# GRLV_DoubleRail_Part2_V0_1.net
KiCad netlist of a schematic drawn in Altium Designer
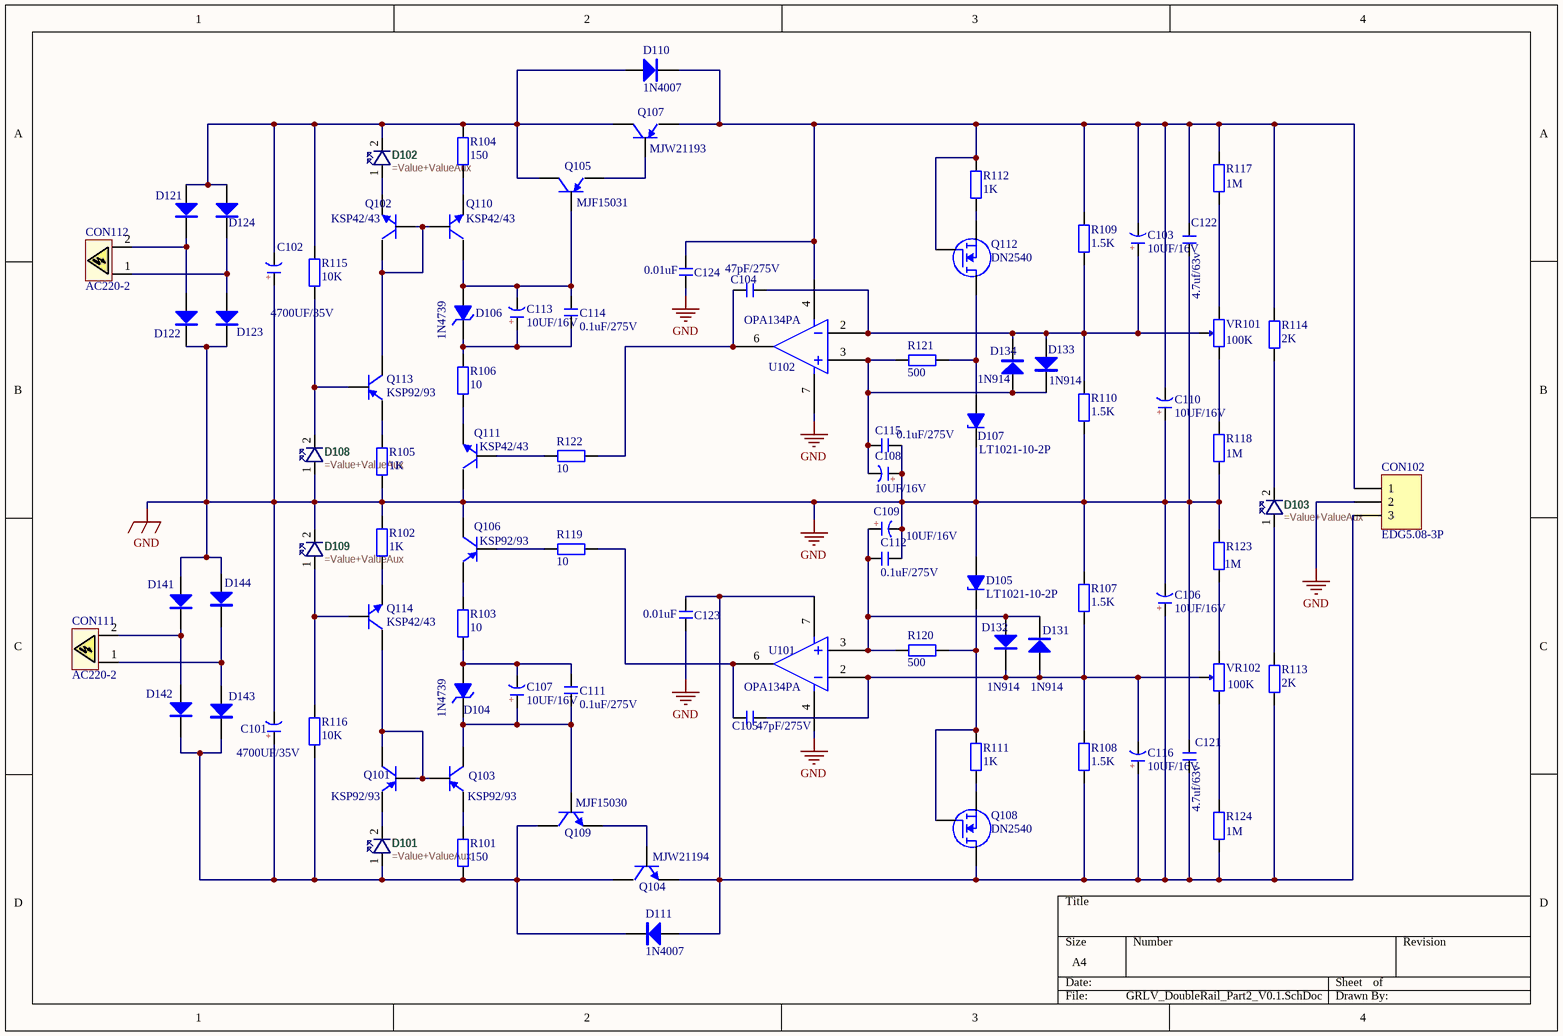
[diagram p0: GRLV_DoubleRail_Part2_V0.1.SchDoc]

(export (version "E")
  (design (tool "Eeschema 10.0.6"))
  (components
    (comp (ref "C101")
      (value "4700UF/35V")
      (footprint "CAP 11*35*60")
      (description "直插电解电容")
      (fields (field (name "版权归属") "源创客"))
      (libsource (lib "电阻-电容-电感") (part "C-CAP"))
    )
    (comp (ref "C102")
      (value "4700UF/35V")
      (footprint "CAP 11*35*60")
      (description "直插电解电容")
      (fields (field (name "版权归属") "源创客"))
      (libsource (lib "电阻-电容-电感") (part "C-CAP"))
    )
    (comp (ref "C103")
      (value "10UF/16V")
      (footprint "CAP 1.5*4*8")
      (description "直插电解电容")
      (fields (field (name "版权归属") "源创客"))
      (libsource (lib "电阻-电容-电感") (part "C-CAP"))
    )
    (comp (ref "C104")
      (value "47pF/275V")
      (footprint "CBB 6.3*6.3*5")
      (description "CBB电容")
      (fields (field (name "版权归属") "源创客"))
      (libsource (lib "电阻-电容-电感") (part "C-CBB"))
    )
    (comp (ref "C105")
      (value "47pF/275V")
      (footprint "CBB 6.3*6.3*5")
      (description "CBB电容")
      (fields (field (name "版权归属") "源创客"))
      (libsource (lib "电阻-电容-电感") (part "C-CBB"))
    )
    (comp (ref "C106")
      (value "10UF/16V")
      (footprint "CAP 3.5*8*11.5")
      (description "直插电解电容")
      (fields (field (name "版权归属") "源创客"))
      (libsource (lib "电阻-电容-电感") (part "C-CAP"))
    )
    (comp (ref "C107")
      (value "10UF/16V")
      (footprint "CAP 1.5*4*8")
      (description "直插电解电容")
      (fields (field (name "版权归属") "源创客"))
      (libsource (lib "电阻-电容-电感") (part "C-CAP"))
    )
    (comp (ref "C108")
      (value "10UF/16V")
      (footprint "CAP 1.5*4*8")
      (description "直插电解电容")
      (fields (field (name "版权归属") "源创客"))
      (libsource (lib "") (part "C-CAP_1"))
    )
    (comp (ref "C109")
      (value "10UF/16V")
      (footprint "CAP 1.5*4*8")
      (description "直插电解电容")
      (fields (field (name "版权归属") "源创客"))
      (libsource (lib "") (part "C-CAP_1"))
    )
    (comp (ref "C110")
      (value "10UF/16V")
      (footprint "CAP 3.5*8*11.5")
      (description "直插电解电容")
      (fields (field (name "版权归属") "源创客"))
      (libsource (lib "电阻-电容-电感") (part "C-CAP"))
    )
    (comp (ref "C111")
      (value "0.1uF/275V")
      (footprint "CBB 6.3*6.3*5")
      (description "CBB电容")
      (fields (field (name "版权归属") "源创客"))
      (libsource (lib "电阻-电容-电感") (part "C-CBB"))
    )
    (comp (ref "C112")
      (value "0.1uF/275V")
      (footprint "CBB 6.3*6.3*5")
      (description "CBB电容")
      (fields (field (name "版权归属") "源创客"))
      (libsource (lib "电阻-电容-电感") (part "C-CBB"))
    )
    (comp (ref "C113")
      (value "10UF/16V")
      (footprint "CAP 1.5*4*8")
      (description "直插电解电容")
      (fields (field (name "版权归属") "源创客"))
      (libsource (lib "电阻-电容-电感") (part "C-CAP"))
    )
    (comp (ref "C114")
      (value "0.1uF/275V")
      (footprint "CBB 6.3*6.3*5")
      (description "CBB电容")
      (fields (field (name "版权归属") "源创客"))
      (libsource (lib "电阻-电容-电感") (part "C-CBB"))
    )
    (comp (ref "C115")
      (value "0.1uF/275V")
      (footprint "CBB 6.3*6.3*5")
      (description "CBB电容")
      (fields (field (name "版权归属") "源创客"))
      (libsource (lib "电阻-电容-电感") (part "C-CBB"))
    )
    (comp (ref "C116")
      (value "10UF/16V")
      (footprint "CAP 1.5*4*8")
      (description "直插电解电容")
      (fields (field (name "版权归属") "源创客"))
      (libsource (lib "电阻-电容-电感") (part "C-CAP"))
    )
    (comp (ref "C121")
      (value "4.7uf/63v")
      (footprint "CBB 7.2*7.2*13")
      (description "MKS薄膜电容")
      (libsource (lib "电阻-电容-电感") (part "C-MKS"))
    )
    (comp (ref "C122")
      (value "4.7uf/63v")
      (footprint "CBB 7.2*7.2*13")
      (description "MKS薄膜电容")
      (libsource (lib "电阻-电容-电感") (part "C-MKS"))
    )
    (comp (ref "C123")
      (value "0.01uF")
      (footprint "CBB 6.3*6.3*5")
      (description "CBB电容")
      (fields (field (name "Comment") "0.01uF/275V") (field (name "版权归属") "源创客"))
      (libsource (lib "电阻-电容-电感") (part "C-CBB"))
    )
    (comp (ref "C124")
      (value "0.01uF")
      (footprint "CBB 6.3*6.3*5")
      (description "CBB电容")
      (fields (field (name "Comment") "0.01uF/275V") (field (name "版权归属") "源创客"))
      (libsource (lib "电阻-电容-电感") (part "C-CBB"))
    )
    (comp (ref "CON102")
      (value "EDG5.08-3P")
      (footprint "HX5.08-3S")
      (libsource (lib "Connectors") (part "EDG5.08-3P"))
    )
    (comp (ref "CON111")
      (value "AC220-2")
      (footprint "HX5.08-2S")
      (libsource (lib "Connectors") (part "AC220-2"))
    )
    (comp (ref "CON112")
      (value "AC220-2")
      (footprint "HX5.08-2S")
      (libsource (lib "Connectors") (part "AC220-2"))
    )
    (comp (ref "D101")
      (value "~")
      (footprint "LED 3MM-R")
      (description "直插式LED")
      (libsource (lib "LED") (part "LED"))
    )
    (comp (ref "D102")
      (value "~")
      (footprint "LED 3MM-R")
      (description "直插式LED")
      (libsource (lib "LED") (part "LED"))
    )
    (comp (ref "D103")
      (value "~")
      (footprint "LED 3MM-R")
      (description "直插式LED")
      (libsource (lib "LED") (part "LED"))
    )
    (comp (ref "D104")
      (value "1N4739")
      (footprint "DO-41")
      (description "9.1V/1W稳压管")
      (libsource (lib "二极管-整流桥") (part "1N4739"))
    )
    (comp (ref "D105")
      (value "LT1021-10-2P")
      (footprint "DIP8-300_MH")
      (description "10V Precision Reference 2 Pin Config")
      (libsource (lib "电压参考") (part "LT1021-10-2P"))
    )
    (comp (ref "D106")
      (value "1N4739")
      (footprint "DO-41")
      (description "9.1V/1W稳压管")
      (libsource (lib "二极管-整流桥") (part "1N4739"))
    )
    (comp (ref "D107")
      (value "LT1021-10-2P")
      (footprint "DIP8-300_MH")
      (description "10V Precision Reference 2 Pin Config")
      (libsource (lib "电压参考") (part "LT1021-10-2P"))
    )
    (comp (ref "D108")
      (value "~")
      (footprint "LED 3MM-R")
      (description "直插式LED")
      (libsource (lib "LED") (part "LED"))
    )
    (comp (ref "D109")
      (value "~")
      (footprint "LED 3MM-R")
      (description "直插式LED")
      (libsource (lib "LED") (part "LED"))
    )
    (comp (ref "D110")
      (value "1N4007")
      (footprint "DO-41")
      (description "整流二极管")
      (fields (field (name "版权归属") "源创客"))
      (libsource (lib "二极管-整流桥") (part "1N4007"))
    )
    (comp (ref "D111")
      (value "1N4007")
      (footprint "DO-41")
      (description "整流二极管")
      (fields (field (name "版权归属") "源创客"))
      (libsource (lib "二极管-整流桥") (part "1N4007"))
    )
    (comp (ref "D121")
      (value "VS-HFA08TB60-M3")
      (footprint "TO220AC")
      (description "Ultrafast Soft Recovery Diado 8A 600V")
      (libsource (lib "二极管-整流桥") (part "VS-HFA08TB60-M3"))
    )
    (comp (ref "D122")
      (value "VS-HFA08TB60-M3")
      (footprint "TO220AC")
      (description "Ultrafast Soft Recovery Diado 8A 600V")
      (libsource (lib "二极管-整流桥") (part "VS-HFA08TB60-M3"))
    )
    (comp (ref "D123")
      (value "VS-HFA08TB60-M3")
      (footprint "TO220AC")
      (description "Ultrafast Soft Recovery Diado 8A 600V")
      (libsource (lib "二极管-整流桥") (part "VS-HFA08TB60-M3"))
    )
    (comp (ref "D124")
      (value "VS-HFA08TB60-M3")
      (footprint "TO220AC")
      (description "Ultrafast Soft Recovery Diado 8A 600V")
      (libsource (lib "二极管-整流桥") (part "VS-HFA08TB60-M3"))
    )
    (comp (ref "D131")
      (value "1N914")
      (footprint "DO-35")
      (description "高速开关管 1V/0.25W")
      (libsource (lib "二极管-整流桥") (part "1N914"))
    )
    (comp (ref "D132")
      (value "1N914")
      (footprint "DO-35")
      (description "高速开关管 1V/0.25W")
      (libsource (lib "二极管-整流桥") (part "1N914"))
    )
    (comp (ref "D133")
      (value "1N914")
      (footprint "DO-35")
      (description "高速开关管 1V/0.25W")
      (libsource (lib "二极管-整流桥") (part "1N914"))
    )
    (comp (ref "D134")
      (value "1N914")
      (footprint "DO-35")
      (description "高速开关管 1V/0.25W")
      (libsource (lib "二极管-整流桥") (part "1N914"))
    )
    (comp (ref "D141")
      (value "VS-HFA08TB60-M3")
      (footprint "TO220AC")
      (description "Ultrafast Soft Recovery Diado 8A 600V")
      (libsource (lib "二极管-整流桥") (part "VS-HFA08TB60-M3"))
    )
    (comp (ref "D142")
      (value "VS-HFA08TB60-M3")
      (footprint "TO220AC")
      (description "Ultrafast Soft Recovery Diado 8A 600V")
      (libsource (lib "二极管-整流桥") (part "VS-HFA08TB60-M3"))
    )
    (comp (ref "D143")
      (value "VS-HFA08TB60-M3")
      (footprint "TO220AC")
      (description "Ultrafast Soft Recovery Diado 8A 600V")
      (libsource (lib "二极管-整流桥") (part "VS-HFA08TB60-M3"))
    )
    (comp (ref "D144")
      (value "VS-HFA08TB60-M3")
      (footprint "TO220AC")
      (description "Ultrafast Soft Recovery Diado 8A 600V")
      (libsource (lib "二极管-整流桥") (part "VS-HFA08TB60-M3"))
    )
    (comp (ref "Q101")
      (value "KSP92/93")
      (footprint "TO92A")
      (description "High Voltage PNP Transistor")
      (libsource (lib "三极管") (part "KSP92/93"))
    )
    (comp (ref "Q102")
      (value "KSP42/43")
      (footprint "TO92A")
      (description "High Voltage NPN Transistor")
      (libsource (lib "三极管") (part "KSP42/43"))
    )
    (comp (ref "Q103")
      (value "KSP92/93")
      (footprint "TO92A")
      (description "High Voltage PNP Transistor")
      (libsource (lib "三极管") (part "KSP92/93"))
    )
    (comp (ref "Q104")
      (value "MJW21194")
      (footprint "TO247V")
      (description "Power NPN Transistor")
      (libsource (lib "三极管") (part "MJW21194"))
    )
    (comp (ref "Q105")
      (value "MJF15031")
      (footprint "TO220V")
      (description "Power PNP Transistor")
      (libsource (lib "三极管") (part "MJF15031"))
    )
    (comp (ref "Q106")
      (value "KSP92/93")
      (footprint "TO92A")
      (description "High Voltage PNP Transistor")
      (libsource (lib "三极管") (part "KSP92/93"))
    )
    (comp (ref "Q107")
      (value "MJW21193")
      (footprint "TO247V")
      (description "Power PNP Transistor")
      (libsource (lib "三极管") (part "MJW21193"))
    )
    (comp (ref "Q108")
      (value "DN2540")
      (footprint "TO92A")
      (description "N沟道耗尽型DMOS场效应管 400V/150ma")
      (libsource (lib "场效应管") (part "DN2540"))
    )
    (comp (ref "Q109")
      (value "MJF15030")
      (footprint "TO220V")
      (description "Power NPN Transistor")
      (libsource (lib "三极管") (part "MJF15030"))
    )
    (comp (ref "Q110")
      (value "KSP42/43")
      (footprint "TO92A")
      (description "High Voltage NPN Transistor")
      (libsource (lib "三极管") (part "KSP42/43"))
    )
    (comp (ref "Q111")
      (value "KSP42/43")
      (footprint "TO92A")
      (description "High Voltage NPN Transistor")
      (libsource (lib "三极管") (part "KSP42/43"))
    )
    (comp (ref "Q112")
      (value "DN2540")
      (footprint "TO92A")
      (description "N沟道耗尽型DMOS场效应管 400V/150ma")
      (libsource (lib "场效应管") (part "DN2540"))
    )
    (comp (ref "Q113")
      (value "KSP92/93")
      (footprint "TO92A")
      (description "High Voltage PNP Transistor")
      (libsource (lib "三极管") (part "KSP92/93"))
    )
    (comp (ref "Q114")
      (value "KSP42/43")
      (footprint "TO92A")
      (description "High Voltage NPN Transistor")
      (libsource (lib "三极管") (part "KSP42/43"))
    )
    (comp (ref "R101")
      (value "150")
      (footprint "RS 1/4W")
      (description "直插色环电阻")
      (fields (field (name "版权归属") "源创客"))
      (libsource (lib "电阻-电容-电感") (part "R-CRR"))
    )
    (comp (ref "R102")
      (value "1K")
      (footprint "RS 1/4W")
      (description "直插色环电阻")
      (fields (field (name "版权归属") "源创客"))
      (libsource (lib "电阻-电容-电感") (part "R-CRR"))
    )
    (comp (ref "R103")
      (value "10")
      (footprint "RS 1/4W")
      (description "直插色环电阻")
      (fields (field (name "版权归属") "源创客"))
      (libsource (lib "电阻-电容-电感") (part "R-CRR"))
    )
    (comp (ref "R104")
      (value "150")
      (footprint "RS 1/4W")
      (description "直插色环电阻")
      (fields (field (name "版权归属") "源创客"))
      (libsource (lib "电阻-电容-电感") (part "R-CRR"))
    )
    (comp (ref "R105")
      (value "1K")
      (footprint "RS 1/4W")
      (description "直插色环电阻")
      (fields (field (name "版权归属") "源创客"))
      (libsource (lib "电阻-电容-电感") (part "R-CRR"))
    )
    (comp (ref "R106")
      (value "10")
      (footprint "RS 1/4W")
      (description "直插色环电阻")
      (fields (field (name "版权归属") "源创客"))
      (libsource (lib "电阻-电容-电感") (part "R-CRR"))
    )
    (comp (ref "R107")
      (value "1.5K")
      (footprint "RS 1/4W")
      (description "直插色环电阻")
      (fields (field (name "版权归属") "源创客"))
      (libsource (lib "电阻-电容-电感") (part "R-CRR"))
    )
    (comp (ref "R108")
      (value "1.5K")
      (footprint "RS 1/4W")
      (description "直插色环电阻")
      (fields (field (name "版权归属") "源创客"))
      (libsource (lib "电阻-电容-电感") (part "R-CRR"))
    )
    (comp (ref "R109")
      (value "1.5K")
      (footprint "RS 1/4W")
      (description "直插色环电阻")
      (fields (field (name "版权归属") "源创客"))
      (libsource (lib "电阻-电容-电感") (part "R-CRR"))
    )
    (comp (ref "R110")
      (value "1.5K")
      (footprint "RS 1/4W")
      (description "直插色环电阻")
      (fields (field (name "版权归属") "源创客"))
      (libsource (lib "电阻-电容-电感") (part "R-CRR"))
    )
    (comp (ref "R111")
      (value "1K")
      (footprint "RS 1/4W")
      (description "直插色环电阻")
      (fields (field (name "版权归属") "源创客"))
      (libsource (lib "电阻-电容-电感") (part "R-CRR"))
    )
    (comp (ref "R112")
      (value "1K")
      (footprint "RS 1/4W")
      (description "直插色环电阻")
      (fields (field (name "版权归属") "源创客"))
      (libsource (lib "电阻-电容-电感") (part "R-CRR"))
    )
    (comp (ref "R113")
      (value "2K")
      (footprint "RS 1/4W")
      (description "直插色环电阻")
      (fields (field (name "版权归属") "源创客"))
      (libsource (lib "电阻-电容-电感") (part "R-CRR"))
    )
    (comp (ref "R114")
      (value "2K")
      (footprint "RS 1/4W")
      (description "直插色环电阻")
      (fields (field (name "版权归属") "源创客"))
      (libsource (lib "电阻-电容-电感") (part "R-CRR"))
    )
    (comp (ref "R115")
      (value "10K")
      (footprint "RS 1/4W")
      (description "直插色环电阻")
      (fields (field (name "版权归属") "源创客"))
      (libsource (lib "电阻-电容-电感") (part "R-CRR"))
    )
    (comp (ref "R116")
      (value "10K")
      (footprint "RS 1/4W")
      (description "直插色环电阻")
      (fields (field (name "版权归属") "源创客"))
      (libsource (lib "电阻-电容-电感") (part "R-CRR"))
    )
    (comp (ref "R117")
      (value "1M")
      (footprint "RS 1/4W")
      (description "直插色环电阻")
      (fields (field (name "版权归属") "源创客"))
      (libsource (lib "电阻-电容-电感") (part "R-CRR"))
    )
    (comp (ref "R118")
      (value "1M")
      (footprint "RS 1/4W")
      (description "直插色环电阻")
      (fields (field (name "版权归属") "源创客"))
      (libsource (lib "电阻-电容-电感") (part "R-CRR"))
    )
    (comp (ref "R119")
      (value "10")
      (footprint "RS 1/4W")
      (description "直插色环电阻")
      (fields (field (name "版权归属") "源创客"))
      (libsource (lib "电阻-电容-电感") (part "R-CRR"))
    )
    (comp (ref "R120")
      (value "500")
      (footprint "RS 1/4W")
      (description "直插色环电阻")
      (fields (field (name "版权归属") "源创客"))
      (libsource (lib "电阻-电容-电感") (part "R-CRR"))
    )
    (comp (ref "R121")
      (value "500")
      (footprint "RS 1/4W")
      (description "直插色环电阻")
      (fields (field (name "版权归属") "源创客"))
      (libsource (lib "电阻-电容-电感") (part "R-CRR"))
    )
    (comp (ref "R122")
      (value "10")
      (footprint "RS 1/4W")
      (description "直插色环电阻")
      (fields (field (name "版权归属") "源创客"))
      (libsource (lib "电阻-电容-电感") (part "R-CRR"))
    )
    (comp (ref "R123")
      (value "1M")
      (footprint "RS 1/4W")
      (description "直插色环电阻")
      (fields (field (name "版权归属") "源创客"))
      (libsource (lib "电阻-电容-电感") (part "R-CRR"))
    )
    (comp (ref "R124")
      (value "1M")
      (footprint "RS 1/4W")
      (description "直插色环电阻")
      (fields (field (name "版权归属") "源创客"))
      (libsource (lib "电阻-电容-电感") (part "R-CRR"))
    )
    (comp (ref "U101") (value "OPA134PA") (footprint "DIP8-300_MH") (libsource (lib "运放") (part "OPA134PA")))
    (comp (ref "U102") (value "OPA134PA") (footprint "DIP8-300_MH") (libsource (lib "运放") (part "OPA134PA")))
    (comp (ref "VR101")
      (value "100K")
      (footprint "RS 1/2W-VR")
      (description "直插可调电阻-顶调")
      (fields (field (name "Comment") "VR-W"))
      (libsource (lib "电阻-电容-电感") (part "VR-W"))
    )
    (comp (ref "VR102")
      (value "100K")
      (footprint "RS 1/2W-VR")
      (description "直插可调电阻-顶调")
      (fields (field (name "Comment") "VR-W"))
      (libsource (lib "电阻-电容-电感") (part "VR-W"))
    )
  )
  (nets
    (net (code "1") (name "GND") (class "Default")
      (node (ref "C101") (pin "2") (pinfunction "K_2") (pintype "passive"))
      (node (ref "C102") (pin "1") (pinfunction "A_1") (pintype "passive"))
      (node (ref "C106") (pin "2") (pinfunction "K_2") (pintype "passive"))
      (node (ref "C108") (pin "1") (pinfunction "A_1") (pintype "passive"))
      (node (ref "C109") (pin "2") (pinfunction "K_2") (pintype "passive"))
      (node (ref "C110") (pin "1") (pinfunction "A_1") (pintype "passive"))
      (node (ref "C112") (pin "2") (pinfunction "2_2") (pintype "passive"))
      (node (ref "C115") (pin "2") (pinfunction "2_2") (pintype "passive"))
      (node (ref "C121") (pin "2") (pinfunction "2_2") (pintype "passive"))
      (node (ref "C122") (pin "1") (pinfunction "1_1") (pintype "passive"))
      (node (ref "C123") (pin "1") (pinfunction "1_1") (pintype "passive"))
      (node (ref "C124") (pin "1") (pinfunction "1_1") (pintype "passive"))
      (node (ref "CON102") (pin "2") (pinfunction "2_2") (pintype "passive"))
      (node (ref "D105") (pin "4") (pinfunction "A_4") (pintype "passive"))
      (node (ref "D107") (pin "6") (pinfunction "K_6") (pintype "passive"))
      (node (ref "D108") (pin "1") (pinfunction "A_1") (pintype "passive"))
      (node (ref "D109") (pin "2") (pinfunction "K_2") (pintype "passive"))
      (node (ref "D122") (pin "1") (pinfunction "Cathode_1") (pintype "passive"))
      (node (ref "D123") (pin "1") (pinfunction "Cathode_1") (pintype "passive"))
      (node (ref "D141") (pin "2") (pinfunction "Anode_2") (pintype "passive"))
      (node (ref "D144") (pin "2") (pinfunction "Anode_2") (pintype "passive"))
      (node (ref "Q106") (pin "3") (pinfunction "C_3") (pintype "passive"))
      (node (ref "Q111") (pin "3") (pinfunction "C_3") (pintype "passive"))
      (node (ref "R102") (pin "2") (pinfunction "2_2") (pintype "passive"))
      (node (ref "R105") (pin "1") (pinfunction "1_1") (pintype "passive"))
      (node (ref "R107") (pin "2") (pinfunction "2_2") (pintype "passive"))
      (node (ref "R110") (pin "1") (pinfunction "1_1") (pintype "passive"))
      (node (ref "R118") (pin "1") (pinfunction "1_1") (pintype "passive"))
      (node (ref "R123") (pin "2") (pinfunction "2_2") (pintype "passive"))
      (node (ref "U101") (pin "4") (pinfunction "V-_4") (pintype "passive"))
      (node (ref "U102") (pin "7") (pinfunction "V+_7") (pintype "passive"))
    )
    (net (code "2") (name "Net-(C101-A)") (class "Default")
      (node (ref "C101") (pin "1") (pinfunction "A_1") (pintype "passive"))
      (node (ref "D101") (pin "1") (pinfunction "A_1") (pintype "passive"))
      (node (ref "D111") (pin "2") (pinfunction "K_2") (pintype "passive"))
      (node (ref "D142") (pin "1") (pinfunction "Cathode_1") (pintype "passive"))
      (node (ref "D143") (pin "1") (pinfunction "Cathode_1") (pintype "passive"))
      (node (ref "Q104") (pin "2") (pinfunction "C_2") (pintype "passive"))
      (node (ref "Q109") (pin "2") (pinfunction "C_2") (pintype "passive"))
      (node (ref "R101") (pin "1") (pinfunction "1_1") (pintype "passive"))
      (node (ref "R116") (pin "1") (pinfunction "1_1") (pintype "passive"))
    )
    (net (code "3") (name "Net-(C102-K)") (class "Default")
      (node (ref "C102") (pin "2") (pinfunction "K_2") (pintype "passive"))
      (node (ref "D102") (pin "2") (pinfunction "K_2") (pintype "passive"))
      (node (ref "D110") (pin "1") (pinfunction "A_1") (pintype "passive"))
      (node (ref "D121") (pin "2") (pinfunction "Anode_2") (pintype "passive"))
      (node (ref "D124") (pin "2") (pinfunction "Anode_2") (pintype "passive"))
      (node (ref "Q105") (pin "2") (pinfunction "C_2") (pintype "passive"))
      (node (ref "Q107") (pin "2") (pinfunction "C_2") (pintype "passive"))
      (node (ref "R104") (pin "2") (pinfunction "2_2") (pintype "passive"))
      (node (ref "R115") (pin "2") (pinfunction "2_2") (pintype "passive"))
    )
    (net (code "4") (name "Net-(C103-A)") (class "Default")
      (node (ref "C103") (pin "1") (pinfunction "A_1") (pintype "passive"))
      (node (ref "C104") (pin "2") (pinfunction "2_2") (pintype "passive"))
      (node (ref "D133") (pin "1") (pinfunction "A_1") (pintype "passive"))
      (node (ref "D134") (pin "2") (pinfunction "K_2") (pintype "passive"))
      (node (ref "R109") (pin "1") (pinfunction "1_1") (pintype "passive"))
      (node (ref "R110") (pin "2") (pinfunction "2_2") (pintype "passive"))
      (node (ref "U102") (pin "2") (pinfunction "-in_2") (pintype "passive"))
      (node (ref "VR101") (pin "3") (pinfunction "3_3") (pintype "passive"))
    )
    (net (code "5") (name "Net-(C103-K)") (class "Default")
      (node (ref "C103") (pin "2") (pinfunction "K_2") (pintype "passive"))
      (node (ref "C110") (pin "2") (pinfunction "K_2") (pintype "passive"))
      (node (ref "C122") (pin "2") (pinfunction "2_2") (pintype "passive"))
      (node (ref "C124") (pin "2") (pinfunction "2_2") (pintype "passive"))
      (node (ref "CON102") (pin "1") (pinfunction "1_1") (pintype "passive"))
      (node (ref "D110") (pin "2") (pinfunction "K_2") (pintype "passive"))
      (node (ref "Q107") (pin "3") (pinfunction "E_3") (pintype "passive"))
      (node (ref "Q112") (pin "2") (pinfunction "G_2") (pintype "passive"))
      (node (ref "R109") (pin "2") (pinfunction "2_2") (pintype "passive"))
      (node (ref "R112") (pin "2") (pinfunction "2_2") (pintype "passive"))
      (node (ref "R114") (pin "2") (pinfunction "2_2") (pintype "passive"))
      (node (ref "R117") (pin "2") (pinfunction "2_2") (pintype "passive"))
      (node (ref "U102") (pin "4") (pinfunction "V-_4") (pintype "passive"))
    )
    (net (code "6") (name "Net-(C106-A)") (class "Default")
      (node (ref "C106") (pin "1") (pinfunction "A_1") (pintype "passive"))
      (node (ref "C116") (pin "1") (pinfunction "A_1") (pintype "passive"))
      (node (ref "C121") (pin "1") (pinfunction "1_1") (pintype "passive"))
      (node (ref "C123") (pin "2") (pinfunction "2_2") (pintype "passive"))
      (node (ref "CON102") (pin "3") (pinfunction "3_3") (pintype "passive"))
      (node (ref "D111") (pin "1") (pinfunction "A_1") (pintype "passive"))
      (node (ref "Q104") (pin "3") (pinfunction "E_3") (pintype "passive"))
      (node (ref "Q108") (pin "3") (pinfunction "D_3") (pintype "passive"))
      (node (ref "R108") (pin "1") (pinfunction "1_1") (pintype "passive"))
      (node (ref "R113") (pin "2") (pinfunction "2_2") (pintype "passive"))
      (node (ref "R124") (pin "1") (pinfunction "1_1") (pintype "passive"))
      (node (ref "U101") (pin "7") (pinfunction "V+_7") (pintype "passive"))
    )
    (net (code "7") (name "Net-(C107-A)") (class "Default")
      (node (ref "C107") (pin "1") (pinfunction "A_1") (pintype "passive"))
      (node (ref "C111") (pin "1") (pinfunction "1_1") (pintype "passive"))
      (node (ref "D104") (pin "2") (pinfunction "K_2") (pintype "passive"))
      (node (ref "Q103") (pin "3") (pinfunction "C_3") (pintype "passive"))
      (node (ref "Q109") (pin "1") (pinfunction "B_1") (pintype "passive"))
    )
    (net (code "8") (name "Net-(C107-K)") (class "Default")
      (node (ref "C107") (pin "2") (pinfunction "K_2") (pintype "passive"))
      (node (ref "C111") (pin "2") (pinfunction "2_2") (pintype "passive"))
      (node (ref "D104") (pin "1") (pinfunction "A_1") (pintype "passive"))
      (node (ref "R103") (pin "1") (pinfunction "1_1") (pintype "passive"))
    )
    (net (code "9") (name "Net-(C108-K)") (class "Default")
      (node (ref "C108") (pin "2") (pinfunction "K_2") (pintype "passive"))
      (node (ref "C115") (pin "1") (pinfunction "1_1") (pintype "passive"))
      (node (ref "D133") (pin "2") (pinfunction "K_2") (pintype "passive"))
      (node (ref "D134") (pin "1") (pinfunction "A_1") (pintype "passive"))
      (node (ref "R121") (pin "1") (pinfunction "1_1") (pintype "passive"))
      (node (ref "U102") (pin "3") (pinfunction "+in_3") (pintype "passive"))
    )
    (net (code "10") (name "Net-(C109-A)") (class "Default")
      (node (ref "C109") (pin "1") (pinfunction "A_1") (pintype "passive"))
      (node (ref "C112") (pin "1") (pinfunction "1_1") (pintype "passive"))
      (node (ref "D131") (pin "2") (pinfunction "K_2") (pintype "passive"))
      (node (ref "D132") (pin "1") (pinfunction "A_1") (pintype "passive"))
      (node (ref "R120") (pin "1") (pinfunction "1_1") (pintype "passive"))
      (node (ref "U101") (pin "3") (pinfunction "+in_3") (pintype "passive"))
    )
    (net (code "11") (name "Net-(C113-A)") (class "Default")
      (node (ref "C113") (pin "1") (pinfunction "A_1") (pintype "passive"))
      (node (ref "C114") (pin "1") (pinfunction "1_1") (pintype "passive"))
      (node (ref "D106") (pin "2") (pinfunction "K_2") (pintype "passive"))
      (node (ref "R106") (pin "2") (pinfunction "2_2") (pintype "passive"))
    )
    (net (code "12") (name "Net-(C113-K)") (class "Default")
      (node (ref "C113") (pin "2") (pinfunction "K_2") (pintype "passive"))
      (node (ref "C114") (pin "2") (pinfunction "2_2") (pintype "passive"))
      (node (ref "D106") (pin "1") (pinfunction "A_1") (pintype "passive"))
      (node (ref "Q105") (pin "1") (pinfunction "B_1") (pintype "passive"))
      (node (ref "Q110") (pin "3") (pinfunction "C_3") (pintype "passive"))
    )
    (net (code "13") (name "Net-(C116-K)") (class "Default")
      (node (ref "C105") (pin "2") (pinfunction "2_2") (pintype "passive"))
      (node (ref "C116") (pin "2") (pinfunction "K_2") (pintype "passive"))
      (node (ref "D131") (pin "1") (pinfunction "A_1") (pintype "passive"))
      (node (ref "D132") (pin "2") (pinfunction "K_2") (pintype "passive"))
      (node (ref "R107") (pin "1") (pinfunction "1_1") (pintype "passive"))
      (node (ref "R108") (pin "2") (pinfunction "2_2") (pintype "passive"))
      (node (ref "U101") (pin "2") (pinfunction "-in_2") (pintype "passive"))
      (node (ref "VR102") (pin "3") (pinfunction "3_3") (pintype "passive"))
    )
    (net (code "14") (name "Net-(CON111-G)") (class "Default")
      (node (ref "CON111") (pin "2") (pinfunction "G_2") (pintype "passive"))
      (node (ref "D141") (pin "1") (pinfunction "Cathode_1") (pintype "passive"))
      (node (ref "D142") (pin "2") (pinfunction "Anode_2") (pintype "passive"))
    )
    (net (code "15") (name "Net-(CON111-L)") (class "Default")
      (node (ref "CON111") (pin "1") (pinfunction "L_1") (pintype "passive"))
      (node (ref "D143") (pin "2") (pinfunction "Anode_2") (pintype "passive"))
      (node (ref "D144") (pin "1") (pinfunction "Cathode_1") (pintype "passive"))
    )
    (net (code "16") (name "Net-(CON112-G)") (class "Default")
      (node (ref "CON112") (pin "2") (pinfunction "G_2") (pintype "passive"))
      (node (ref "D121") (pin "1") (pinfunction "Cathode_1") (pintype "passive"))
      (node (ref "D122") (pin "2") (pinfunction "Anode_2") (pintype "passive"))
    )
    (net (code "17") (name "Net-(CON112-L)") (class "Default")
      (node (ref "CON112") (pin "1") (pinfunction "L_1") (pintype "passive"))
      (node (ref "D123") (pin "2") (pinfunction "Anode_2") (pintype "passive"))
      (node (ref "D124") (pin "1") (pinfunction "Cathode_1") (pintype "passive"))
    )
    (net (code "18") (name "Net-(D101-K)") (class "Default")
      (node (ref "D101") (pin "2") (pinfunction "K_2") (pintype "passive"))
      (node (ref "Q101") (pin "1") (pinfunction "E_1") (pintype "passive"))
    )
    (net (code "19") (name "Net-(D102-A)") (class "Default")
      (node (ref "D102") (pin "1") (pinfunction "A_1") (pintype "passive"))
      (node (ref "Q102") (pin "1") (pinfunction "E_1") (pintype "passive"))
    )
    (net (code "20") (name "Net-(D103-A)") (class "Default")
      (node (ref "D103") (pin "1") (pinfunction "A_1") (pintype "passive"))
      (node (ref "R113") (pin "1") (pinfunction "1_1") (pintype "passive"))
    )
    (net (code "21") (name "Net-(D103-K)") (class "Default")
      (node (ref "D103") (pin "2") (pinfunction "K_2") (pintype "passive"))
      (node (ref "R114") (pin "1") (pinfunction "1_1") (pintype "passive"))
    )
    (net (code "22") (name "Net-(D105-K)") (class "Default")
      (node (ref "D105") (pin "6") (pinfunction "K_6") (pintype "passive"))
      (node (ref "Q108") (pin "2") (pinfunction "G_2") (pintype "passive"))
      (node (ref "R111") (pin "2") (pinfunction "2_2") (pintype "passive"))
      (node (ref "R120") (pin "2") (pinfunction "2_2") (pintype "passive"))
    )
    (net (code "23") (name "Net-(D107-A)") (class "Default")
      (node (ref "D107") (pin "4") (pinfunction "A_4") (pintype "passive"))
      (node (ref "Q112") (pin "3") (pinfunction "D_3") (pintype "passive"))
      (node (ref "R121") (pin "2") (pinfunction "2_2") (pintype "passive"))
    )
    (net (code "24") (name "Net-(D108-K)") (class "Default")
      (node (ref "D108") (pin "2") (pinfunction "K_2") (pintype "passive"))
      (node (ref "Q113") (pin "2") (pinfunction "B_2") (pintype "passive"))
      (node (ref "R115") (pin "1") (pinfunction "1_1") (pintype "passive"))
    )
    (net (code "25") (name "Net-(D109-A)") (class "Default")
      (node (ref "D109") (pin "1") (pinfunction "A_1") (pintype "passive"))
      (node (ref "Q114") (pin "2") (pinfunction "B_2") (pintype "passive"))
      (node (ref "R116") (pin "2") (pinfunction "2_2") (pintype "passive"))
    )
    (net (code "26") (name "Net-(Q101-B)") (class "Default")
      (node (ref "Q101") (pin "2") (pinfunction "B_2") (pintype "passive"))
      (node (ref "Q101") (pin "3") (pinfunction "C_3") (pintype "passive"))
      (node (ref "Q103") (pin "2") (pinfunction "B_2") (pintype "passive"))
      (node (ref "Q114") (pin "3") (pinfunction "C_3") (pintype "passive"))
    )
    (net (code "27") (name "Net-(Q102-B)") (class "Default")
      (node (ref "Q102") (pin "2") (pinfunction "B_2") (pintype "passive"))
      (node (ref "Q102") (pin "3") (pinfunction "C_3") (pintype "passive"))
      (node (ref "Q110") (pin "2") (pinfunction "B_2") (pintype "passive"))
      (node (ref "Q113") (pin "3") (pinfunction "C_3") (pintype "passive"))
    )
    (net (code "28") (name "Net-(Q103-E)") (class "Default")
      (node (ref "Q103") (pin "1") (pinfunction "E_1") (pintype "passive"))
      (node (ref "R101") (pin "2") (pinfunction "2_2") (pintype "passive"))
    )
    (net (code "29") (name "Net-(Q104-B)") (class "Default")
      (node (ref "Q104") (pin "1") (pinfunction "B_1") (pintype "passive"))
      (node (ref "Q109") (pin "3") (pinfunction "E_3") (pintype "passive"))
    )
    (net (code "30") (name "Net-(Q105-E)") (class "Default")
      (node (ref "Q105") (pin "3") (pinfunction "E_3") (pintype "passive"))
      (node (ref "Q107") (pin "1") (pinfunction "B_1") (pintype "passive"))
    )
    (net (code "31") (name "Net-(Q106-B)") (class "Default")
      (node (ref "Q106") (pin "2") (pinfunction "B_2") (pintype "passive"))
      (node (ref "R119") (pin "1") (pinfunction "1_1") (pintype "passive"))
    )
    (net (code "32") (name "Net-(Q106-E)") (class "Default")
      (node (ref "Q106") (pin "1") (pinfunction "E_1") (pintype "passive"))
      (node (ref "R103") (pin "2") (pinfunction "2_2") (pintype "passive"))
    )
    (net (code "33") (name "Net-(Q108-S)") (class "Default")
      (node (ref "Q108") (pin "1") (pinfunction "S_1") (pintype "passive"))
      (node (ref "R111") (pin "1") (pinfunction "1_1") (pintype "passive"))
    )
    (net (code "34") (name "Net-(Q110-E)") (class "Default")
      (node (ref "Q110") (pin "1") (pinfunction "E_1") (pintype "passive"))
      (node (ref "R104") (pin "1") (pinfunction "1_1") (pintype "passive"))
    )
    (net (code "35") (name "Net-(Q111-B)") (class "Default")
      (node (ref "Q111") (pin "2") (pinfunction "B_2") (pintype "passive"))
      (node (ref "R122") (pin "1") (pinfunction "1_1") (pintype "passive"))
    )
    (net (code "36") (name "Net-(Q111-E)") (class "Default")
      (node (ref "Q111") (pin "1") (pinfunction "E_1") (pintype "passive"))
      (node (ref "R106") (pin "1") (pinfunction "1_1") (pintype "passive"))
    )
    (net (code "37") (name "Net-(Q112-S)") (class "Default")
      (node (ref "Q112") (pin "1") (pinfunction "S_1") (pintype "passive"))
      (node (ref "R112") (pin "1") (pinfunction "1_1") (pintype "passive"))
    )
    (net (code "38") (name "Net-(Q113-E)") (class "Default")
      (node (ref "Q113") (pin "1") (pinfunction "E_1") (pintype "passive"))
      (node (ref "R105") (pin "2") (pinfunction "2_2") (pintype "passive"))
    )
    (net (code "39") (name "Net-(Q114-E)") (class "Default")
      (node (ref "Q114") (pin "1") (pinfunction "E_1") (pintype "passive"))
      (node (ref "R102") (pin "1") (pinfunction "1_1") (pintype "passive"))
    )
    (net (code "40") (name "Net-(R117-Pad1)") (class "Default")
      (node (ref "R117") (pin "1") (pinfunction "1_1") (pintype "passive"))
      (node (ref "VR101") (pin "2") (pinfunction "2_2") (pintype "passive"))
    )
    (net (code "41") (name "Net-(R118-Pad2)") (class "Default")
      (node (ref "R118") (pin "2") (pinfunction "2_2") (pintype "passive"))
      (node (ref "VR101") (pin "1") (pinfunction "1_1") (pintype "passive"))
    )
    (net (code "42") (name "Net-(R123-Pad1)") (class "Default")
      (node (ref "R123") (pin "1") (pinfunction "1_1") (pintype "passive"))
      (node (ref "VR102") (pin "2") (pinfunction "2_2") (pintype "passive"))
    )
    (net (code "43") (name "Net-(R124-Pad2)") (class "Default")
      (node (ref "R124") (pin "2") (pinfunction "2_2") (pintype "passive"))
      (node (ref "VR102") (pin "1") (pinfunction "1_1") (pintype "passive"))
    )
    (net (code "44") (name "Net-(U101-out)") (class "Default")
      (node (ref "C105") (pin "1") (pinfunction "1_1") (pintype "passive"))
      (node (ref "R119") (pin "2") (pinfunction "2_2") (pintype "passive"))
      (node (ref "U101") (pin "6") (pinfunction "out_6") (pintype "passive"))
    )
    (net (code "45") (name "Net-(U102-out)") (class "Default")
      (node (ref "C104") (pin "1") (pinfunction "1_1") (pintype "passive"))
      (node (ref "R122") (pin "2") (pinfunction "2_2") (pintype "passive"))
      (node (ref "U102") (pin "6") (pinfunction "out_6") (pintype "passive"))
    )
  )
)
